# PAGE1old.net
KiCad netlist of a schematic drawn in Altium Designer
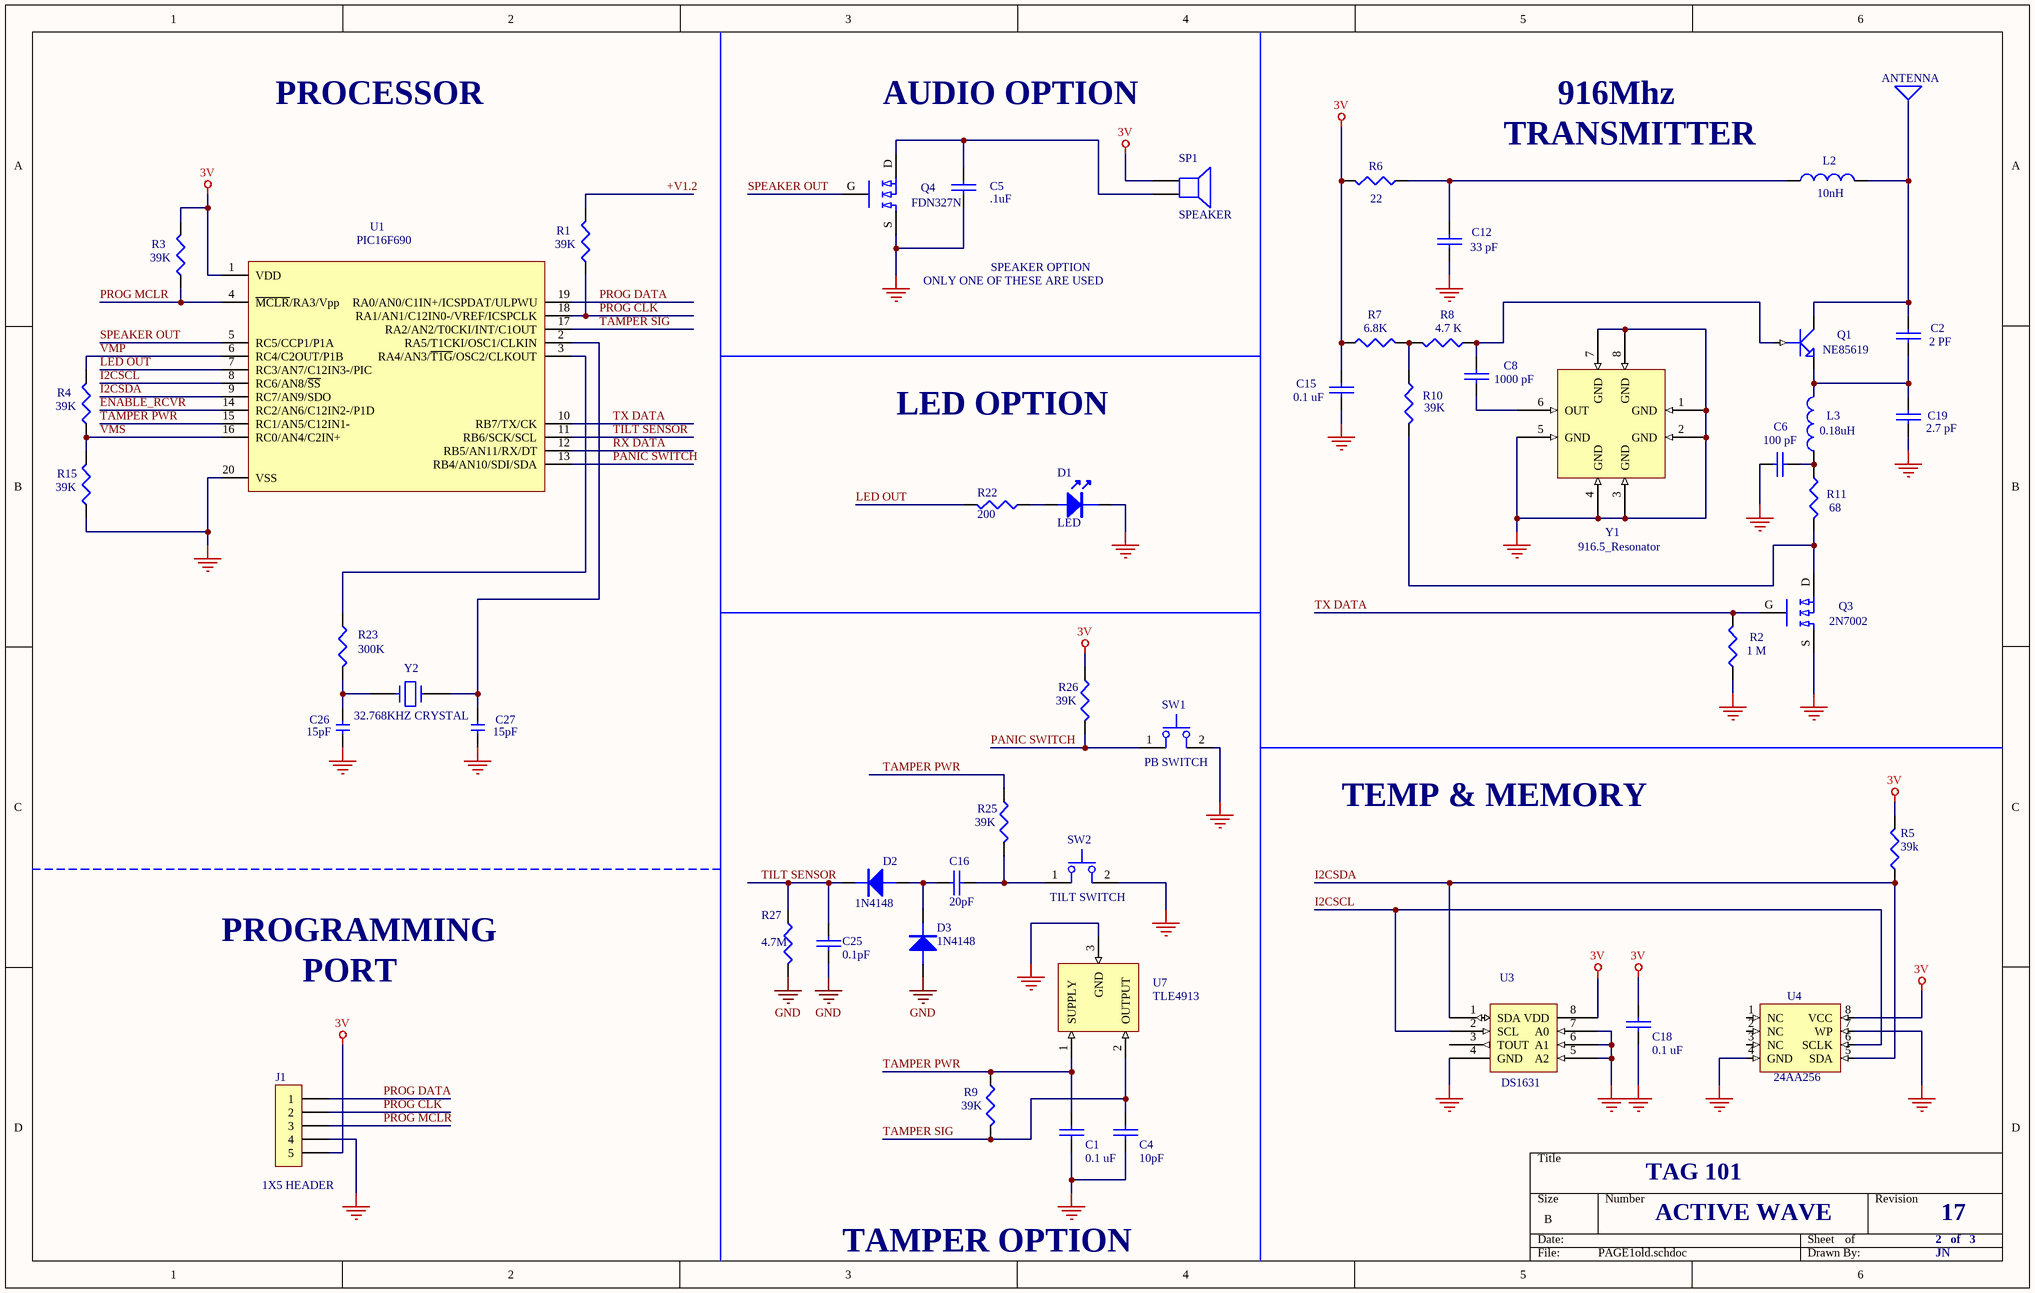
[diagram p0: PAGE1old.schdoc]

(export (version "E")
  (design (tool "Eeschema 10.0.6"))
  (components
    (comp (ref "C1")
      (value "0.1 uF")
      (footprint "0603")
      (description "Capacitor")
      (libsource (lib "*") (part "CAP"))
    )
    (comp (ref "C2")
      (value "2 PF")
      (footprint "0603")
      (description "Capacitor")
      (libsource (lib "*") (part "CAP"))
    )
    (comp (ref "C4")
      (value "10pF")
      (footprint "0603")
      (description "Capacitor")
      (libsource (lib "*") (part "CAP"))
    )
    (comp (ref "C5")
      (value ".1uF")
      (footprint "0603")
      (description "Capacitor")
      (libsource (lib "*") (part "CAP"))
    )
    (comp (ref "C6")
      (value "100 pF")
      (footprint "0603")
      (description "Capacitor")
      (libsource (lib "*") (part "CAP"))
    )
    (comp (ref "C8")
      (value "1000 pF")
      (footprint "0603")
      (description "Capacitor")
      (libsource (lib "*") (part "CAP"))
    )
    (comp (ref "C12")
      (value "33 pF")
      (footprint "0603")
      (description "Capacitor")
      (libsource (lib "*") (part "CAP"))
    )
    (comp (ref "C15")
      (value "0.1 uF")
      (footprint "0603")
      (description "Capacitor")
      (libsource (lib "*") (part "CAP"))
    )
    (comp (ref "C16")
      (value "20pF")
      (footprint "0603")
      (description "Capacitor")
      (libsource (lib "*") (part "CAP"))
    )
    (comp (ref "C18")
      (value "0.1 uF")
      (footprint "0603")
      (description "Capacitor")
      (libsource (lib "*") (part "CAP"))
    )
    (comp (ref "C19")
      (value "2.7 pF")
      (footprint "0603")
      (description "Capacitor")
      (libsource (lib "*") (part "CAP"))
    )
    (comp (ref "C25")
      (value "0.1pF")
      (footprint "0603")
      (description "Capacitor")
      (libsource (lib "*") (part "CAP"))
    )
    (comp (ref "C26") (value "15pF") (footprint "0603") (libsource (lib "*") (part "C")))
    (comp (ref "C27") (value "15pF") (footprint "0603") (libsource (lib "*") (part "C")))
    (comp (ref "D1") (value "LED") (footprint "LED STANLEY H_1105W") (libsource (lib "*") (part "LED")))
    (comp (ref "D2")
      (value "1N4148")
      (footprint "sod123_021405")
      (description "Diode")
      (libsource (lib "*") (part "DIODE"))
    )
    (comp (ref "D3")
      (value "1N4148")
      (footprint "sod123_021405")
      (description "Diode")
      (libsource (lib "*") (part "DIODE"))
    )
    (comp (ref "J1")
      (value "1X5 HEADER")
      (footprint "1X5 HEADER")
      (description "Connector")
      (libsource (lib "*") (part "CON5"))
    )
    (comp (ref "L2") (value "10nH") (footprint "0603") (libsource (lib "*") (part "INDUCTOR")))
    (comp (ref "L3") (value "0.18uH") (footprint "0603") (libsource (lib "*") (part "INDUCTOR")))
    (comp (ref "Q1")
      (value "NE85619")
      (footprint "3 PIN ULTRA SUPER MINI MOLD")
      (description "NPN Transistor")
      (libsource (lib "*") (part "NPN1"))
    )
    (comp (ref "Q3") (value "2N7002") (libsource (lib "*") (part "FET 2")))
    (comp (ref "Q4") (value "FDN327N") (libsource (lib "*") (part "FET 2")))
    (comp (ref "R1") (value "39K") (footprint "0603") (libsource (lib "*") (part "RESISTOR")))
    (comp (ref "R2") (value "1 M") (footprint "0603") (libsource (lib "*") (part "RESISTOR")))
    (comp (ref "R3") (value "39K") (footprint "0603") (libsource (lib "*") (part "RESISTOR")))
    (comp (ref "R4") (value "39K") (footprint "0603") (libsource (lib "*") (part "RESISTOR")))
    (comp (ref "R5") (value "39k") (footprint "0603") (libsource (lib "*") (part "RESISTOR")))
    (comp (ref "R6") (value "22") (footprint "0603") (libsource (lib "*") (part "RESISTOR")))
    (comp (ref "R7") (value "6.8K") (footprint "0603") (libsource (lib "*") (part "RESISTOR")))
    (comp (ref "R8") (value "4.7 K") (footprint "0603") (libsource (lib "*") (part "RESISTOR")))
    (comp (ref "R9") (value "39K") (footprint "0603") (libsource (lib "*") (part "RESISTOR")))
    (comp (ref "R10") (value "39K") (footprint "0603") (libsource (lib "*") (part "RESISTOR")))
    (comp (ref "R11") (value "68") (footprint "0603") (libsource (lib "*") (part "RES1")))
    (comp (ref "R15") (value "39K") (footprint "0603") (libsource (lib "*") (part "RESISTOR")))
    (comp (ref "R22") (value "200") (footprint "0603") (libsource (lib "*") (part "RES1")))
    (comp (ref "R23") (value "300K") (footprint "0603") (libsource (lib "*") (part "RESISTOR")))
    (comp (ref "R25") (value "39K") (footprint "0603") (libsource (lib "*") (part "RESISTOR")))
    (comp (ref "R26") (value "39K") (footprint "0603") (libsource (lib "*") (part "RESISTOR")))
    (comp (ref "R27") (value "4.7M") (footprint "0603") (libsource (lib "*") (part "RESISTOR")))
    (comp (ref "SP1") (value "SPEAKER") (footprint "SMT_1028-S-R") (libsource (lib "*") (part "SPEAKER")))
    (comp (ref "SW1")
      (value "PB SWITCH")
      (footprint "SWITCH PB REVERSED_082907")
      (libsource (lib "Common") (part "SWITCH PB"))
    )
    (comp (ref "SW2")
      (value "TILT SWITCH")
      (footprint "SQ-SEN-200")
      (libsource (lib "Common") (part "SWITCH PB"))
    )
    (comp (ref "U1") (value "PIC16F690") (libsource (lib "*") (part "PIC16F690")))
    (comp (ref "U3") (value "DS1631") (footprint "SO8 SMALL") (libsource (lib "*") (part "DS1631")))
    (comp (ref "U4") (value "24AA256") (footprint "SO8") (libsource (lib "*") (part "24AA256")))
    (comp (ref "U7") (value "TLE4913") (footprint "SOT23W") (libsource (lib "*") (part "HALL EFFECT SWITCH")))
    (comp (ref "Y1")
      (value "916.5_Resonator")
      (footprint "RESONATOR")
      (libsource (lib "*") (part "RESONATOR"))
    )
    (comp (ref "Y2")
      (value "32.768KHZ CRYSTAL")
      (footprint "CRYSTAL ABRACON ABS07")
      (description "Crystal")
      (libsource (lib "*") (part "CRYSTAL"))
    )
  )
  (nets
    (net (code "1") (name "/+V1.2") (class "Default")
      (node (ref "R1") (pin "2") (pinfunction "2_2") (pintype "passive"))
    )
    (net (code "2") (name "/ENABLE_RCVR") (class "Default")
      (node (ref "U1") (pin "14") (pinfunction "RC2/AN6/C12IN2-/P1D_14") (pintype "passive"))
    )
    (net (code "3") (name "/I2CSCL") (class "Default")
      (node (ref "U1") (pin "8") (pinfunction "RC6/AN8/~{SS}_8") (pintype "passive"))
      (node (ref "U3") (pin "2") (pinfunction "SCL_2") (pintype "input"))
      (node (ref "U4") (pin "6") (pinfunction "SCLK_6") (pintype "input"))
    )
    (net (code "4") (name "/I2CSDA") (class "Default")
      (node (ref "R5") (pin "1") (pinfunction "1_1") (pintype "passive"))
      (node (ref "U1") (pin "9") (pinfunction "RC7/AN9/SDO_9") (pintype "passive"))
      (node (ref "U3") (pin "1") (pinfunction "SDA_1") (pintype "bidirectional"))
      (node (ref "U4") (pin "5") (pinfunction "SDA_5") (pintype "input"))
    )
    (net (code "5") (name "/LED OUT") (class "Default")
      (node (ref "R22") (pin "2") (pinfunction "2_2") (pintype "passive"))
      (node (ref "U1") (pin "7") (pinfunction "RC3/AN7/C12IN3-/PIC_7") (pintype "passive"))
    )
    (net (code "6") (name "/PANIC SWITCH") (class "Default")
      (node (ref "R26") (pin "2") (pinfunction "2_2") (pintype "passive"))
      (node (ref "SW1") (pin "1") (pinfunction "1_1") (pintype "passive"))
      (node (ref "U1") (pin "13") (pinfunction "RB4/AN10/SDI/SDA_13") (pintype "passive"))
    )
    (net (code "7") (name "/PROG CLK") (class "Default")
      (node (ref "J1") (pin "2") (pinfunction "2_2") (pintype "passive"))
      (node (ref "R1") (pin "1") (pinfunction "1_1") (pintype "passive"))
      (node (ref "U1") (pin "18") (pinfunction "RA1/AN1/C12IN0-/VREF/ICSPCLK_18") (pintype "passive"))
    )
    (net (code "8") (name "/PROG DATA") (class "Default")
      (node (ref "J1") (pin "1") (pinfunction "1_1") (pintype "passive"))
      (node (ref "U1") (pin "19") (pinfunction "RA0/AN0/C1IN+/ICSPDAT/ULPWU_19") (pintype "passive"))
    )
    (net (code "9") (name "/PROG MCLR") (class "Default")
      (node (ref "J1") (pin "3") (pinfunction "3_3") (pintype "passive"))
      (node (ref "R3") (pin "1") (pinfunction "1_1") (pintype "passive"))
      (node (ref "U1") (pin "4") (pinfunction "~{MCLR}/RA3/Vpp_4") (pintype "passive"))
    )
    (net (code "10") (name "/RX DATA") (class "Default")
      (node (ref "U1") (pin "12") (pinfunction "RB5/AN11/RX/DT_12") (pintype "passive"))
    )
    (net (code "11") (name "/SPEAKER OUT") (class "Default")
      (node (ref "Q4") (pin "G") (pinfunction "G_G") (pintype "passive"))
      (node (ref "U1") (pin "5") (pinfunction "RC5/CCP1/P1A_5") (pintype "passive"))
    )
    (net (code "12") (name "/TAMPER PWR") (class "Default")
      (node (ref "C1") (pin "1") (pinfunction "1_1") (pintype "passive"))
      (node (ref "R25") (pin "1") (pinfunction "1_1") (pintype "passive"))
      (node (ref "R9") (pin "1") (pinfunction "1_1") (pintype "passive"))
      (node (ref "U1") (pin "15") (pinfunction "RC1/AN5/C12IN1-_15") (pintype "passive"))
      (node (ref "U7") (pin "1") (pinfunction "SUPPLY_1") (pintype "input"))
    )
    (net (code "13") (name "/TAMPER SIG") (class "Default")
      (node (ref "C4") (pin "1") (pinfunction "1_1") (pintype "passive"))
      (node (ref "R9") (pin "2") (pinfunction "2_2") (pintype "passive"))
      (node (ref "U1") (pin "17") (pinfunction "RA2/AN2/T0CKI/INT/C1OUT_17") (pintype "passive"))
      (node (ref "U7") (pin "2") (pinfunction "OUTPUT_2") (pintype "input"))
    )
    (net (code "14") (name "/TILT SENSOR") (class "Default")
      (node (ref "C25") (pin "1") (pinfunction "1_1") (pintype "passive"))
      (node (ref "D2") (pin "K") (pinfunction "K_K") (pintype "passive"))
      (node (ref "R27") (pin "1") (pinfunction "1_1") (pintype "passive"))
      (node (ref "U1") (pin "11") (pinfunction "RB6/SCK/SCL_11") (pintype "passive"))
    )
    (net (code "15") (name "/TX DATA") (class "Default")
      (node (ref "Q3") (pin "G") (pinfunction "G_G") (pintype "passive"))
      (node (ref "R2") (pin "2") (pinfunction "2_2") (pintype "passive"))
      (node (ref "U1") (pin "10") (pinfunction "RB7/TX/CK_10") (pintype "passive"))
    )
    (net (code "16") (name "/VMP") (class "Default")
      (node (ref "R4") (pin "2") (pinfunction "2_2") (pintype "passive"))
      (node (ref "U1") (pin "6") (pinfunction "RC4/C2OUT/P1B_6") (pintype "passive"))
    )
    (net (code "17") (name "/VMS") (class "Default")
      (node (ref "R15") (pin "2") (pinfunction "2_2") (pintype "passive"))
      (node (ref "R4") (pin "1") (pinfunction "1_1") (pintype "passive"))
      (node (ref "U1") (pin "16") (pinfunction "RC0/AN4/C2IN+_16") (pintype "passive"))
    )
    (net (code "18") (name "3V") (class "Default")
      (node (ref "C15") (pin "1") (pinfunction "1_1") (pintype "passive"))
      (node (ref "C18") (pin "1") (pinfunction "1_1") (pintype "passive"))
      (node (ref "J1") (pin "5") (pinfunction "5_5") (pintype "passive"))
      (node (ref "R26") (pin "1") (pinfunction "1_1") (pintype "passive"))
      (node (ref "R3") (pin "2") (pinfunction "2_2") (pintype "passive"))
      (node (ref "R5") (pin "2") (pinfunction "2_2") (pintype "passive"))
      (node (ref "R6") (pin "2") (pinfunction "2_2") (pintype "passive"))
      (node (ref "R7") (pin "1") (pinfunction "1_1") (pintype "passive"))
      (node (ref "SP1") (pin "1") (pinfunction "1_1") (pintype "passive"))
      (node (ref "U1") (pin "1") (pinfunction "VDD_1") (pintype "passive"))
      (node (ref "U3") (pin "8") (pinfunction "VDD_8") (pintype "power_in"))
      (node (ref "U4") (pin "8") (pinfunction "VCC_8") (pintype "input"))
    )
    (net (code "19") (name "GND") (class "Default")
      (node (ref "C1") (pin "2") (pinfunction "2_2") (pintype "passive"))
      (node (ref "C12") (pin "2") (pinfunction "2_2") (pintype "passive"))
      (node (ref "C15") (pin "2") (pinfunction "2_2") (pintype "passive"))
      (node (ref "C18") (pin "2") (pinfunction "2_2") (pintype "passive"))
      (node (ref "C19") (pin "2") (pinfunction "2_2") (pintype "passive"))
      (node (ref "C25") (pin "2") (pinfunction "2_2") (pintype "passive"))
      (node (ref "C26") (pin "1") (pinfunction "1_1") (pintype "passive"))
      (node (ref "C27") (pin "1") (pinfunction "1_1") (pintype "passive"))
      (node (ref "C4") (pin "2") (pinfunction "2_2") (pintype "passive"))
      (node (ref "C5") (pin "2") (pinfunction "2_2") (pintype "passive"))
      (node (ref "C6") (pin "1") (pinfunction "1_1") (pintype "passive"))
      (node (ref "D1") (pin "K") (pinfunction "K_K") (pintype "passive"))
      (node (ref "D3") (pin "A") (pinfunction "A_A") (pintype "passive"))
      (node (ref "J1") (pin "4") (pinfunction "4_4") (pintype "passive"))
      (node (ref "Q3") (pin "S") (pinfunction "S_S") (pintype "passive"))
      (node (ref "Q4") (pin "S") (pinfunction "S_S") (pintype "passive"))
      (node (ref "R15") (pin "1") (pinfunction "1_1") (pintype "passive"))
      (node (ref "R2") (pin "1") (pinfunction "1_1") (pintype "passive"))
      (node (ref "R27") (pin "2") (pinfunction "2_2") (pintype "passive"))
      (node (ref "SW1") (pin "2") (pinfunction "2_2") (pintype "passive"))
      (node (ref "SW2") (pin "2") (pinfunction "2_2") (pintype "passive"))
      (node (ref "U1") (pin "20") (pinfunction "VSS_20") (pintype "passive"))
      (node (ref "U3") (pin "4") (pinfunction "GND_4") (pintype "power_in"))
      (node (ref "U3") (pin "5") (pinfunction "A2_5") (pintype "input"))
      (node (ref "U3") (pin "6") (pinfunction "A1_6") (pintype "input"))
      (node (ref "U3") (pin "7") (pinfunction "A0_7") (pintype "input"))
      (node (ref "U4") (pin "4") (pinfunction "GND_4") (pintype "input"))
      (node (ref "U4") (pin "7") (pinfunction "WP_7") (pintype "input"))
      (node (ref "U7") (pin "3") (pinfunction "GND_3") (pintype "input"))
      (node (ref "Y1") (pin "1") (pinfunction "GND_1") (pintype "input"))
      (node (ref "Y1") (pin "2") (pinfunction "GND_2") (pintype "input"))
      (node (ref "Y1") (pin "3") (pinfunction "GND_3") (pintype "input"))
      (node (ref "Y1") (pin "4") (pinfunction "GND_4") (pintype "input"))
      (node (ref "Y1") (pin "5") (pinfunction "GND_5") (pintype "input"))
      (node (ref "Y1") (pin "7") (pinfunction "GND_7") (pintype "input"))
      (node (ref "Y1") (pin "8") (pinfunction "GND_8") (pintype "input"))
    )
    (net (code "20") (name "Net-(C2-Pad1)") (class "Default")
      (node (ref "C2") (pin "1") (pinfunction "1_1") (pintype "passive"))
      (node (ref "L2") (pin "2") (pinfunction "2_2") (pintype "passive"))
      (node (ref "Q1") (pin "C") (pinfunction "C_C") (pintype "passive"))
    )
    (net (code "21") (name "Net-(C5-Pad1)") (class "Default")
      (node (ref "C5") (pin "1") (pinfunction "1_1") (pintype "passive"))
      (node (ref "Q4") (pin "D") (pinfunction "D_D") (pintype "passive"))
      (node (ref "SP1") (pin "2") (pinfunction "2_2") (pintype "passive"))
    )
    (net (code "22") (name "Net-(C6-Pad2)") (class "Default")
      (node (ref "C6") (pin "2") (pinfunction "2_2") (pintype "passive"))
      (node (ref "L3") (pin "1") (pinfunction "1_1") (pintype "passive"))
      (node (ref "R11") (pin "1") (pinfunction "1_1") (pintype "passive"))
    )
    (net (code "23") (name "Net-(C8-Pad1)") (class "Default")
      (node (ref "C8") (pin "1") (pinfunction "1_1") (pintype "passive"))
      (node (ref "Q1") (pin "B") (pinfunction "B_B") (pintype "input"))
      (node (ref "R8") (pin "1") (pinfunction "1_1") (pintype "passive"))
    )
    (net (code "24") (name "Net-(C12-Pad1)") (class "Default")
      (node (ref "C12") (pin "1") (pinfunction "1_1") (pintype "passive"))
      (node (ref "L2") (pin "1") (pinfunction "1_1") (pintype "passive"))
      (node (ref "R6") (pin "1") (pinfunction "1_1") (pintype "passive"))
    )
    (net (code "25") (name "Net-(C16-Pad1)") (class "Default")
      (node (ref "C16") (pin "1") (pinfunction "1_1") (pintype "passive"))
      (node (ref "R25") (pin "2") (pinfunction "2_2") (pintype "passive"))
      (node (ref "SW2") (pin "1") (pinfunction "1_1") (pintype "passive"))
    )
    (net (code "26") (name "Net-(C16-Pad2)") (class "Default")
      (node (ref "C16") (pin "2") (pinfunction "2_2") (pintype "passive"))
      (node (ref "D2") (pin "A") (pinfunction "A_A") (pintype "passive"))
      (node (ref "D3") (pin "K") (pinfunction "K_K") (pintype "passive"))
    )
    (net (code "27") (name "Net-(C19-Pad1)") (class "Default")
      (node (ref "C19") (pin "1") (pinfunction "1_1") (pintype "passive"))
      (node (ref "C2") (pin "2") (pinfunction "2_2") (pintype "passive"))
      (node (ref "L3") (pin "2") (pinfunction "2_2") (pintype "passive"))
      (node (ref "Q1") (pin "E") (pinfunction "E_E") (pintype "passive"))
    )
    (net (code "28") (name "Net-(C26-Pad2)") (class "Default")
      (node (ref "C26") (pin "2") (pinfunction "2_2") (pintype "passive"))
      (node (ref "R23") (pin "2") (pinfunction "2_2") (pintype "passive"))
      (node (ref "Y2") (pin "2") (pinfunction "2_2") (pintype "passive"))
    )
    (net (code "29") (name "Net-(D1-PadA)") (class "Default")
      (node (ref "D1") (pin "A") (pinfunction "A_A") (pintype "passive"))
      (node (ref "R22") (pin "1") (pinfunction "1_1") (pintype "passive"))
    )
    (net (code "30") (name "Net-(Q3-PadD)") (class "Default")
      (node (ref "Q3") (pin "D") (pinfunction "D_D") (pintype "passive"))
      (node (ref "R10") (pin "2") (pinfunction "2_2") (pintype "passive"))
      (node (ref "R11") (pin "2") (pinfunction "2_2") (pintype "passive"))
    )
    (net (code "31") (name "Net-(R10-Pad1)") (class "Default")
      (node (ref "R10") (pin "1") (pinfunction "1_1") (pintype "passive"))
      (node (ref "R7") (pin "2") (pinfunction "2_2") (pintype "passive"))
      (node (ref "R8") (pin "2") (pinfunction "2_2") (pintype "passive"))
    )
    (net (code "32") (name "Net-(U1-RA4{slash}AN3{slash}~{T1G}{slash}OSC2{slash}CLKOUT)") (class "Default")
      (node (ref "R23") (pin "1") (pinfunction "1_1") (pintype "passive"))
      (node (ref "U1") (pin "3") (pinfunction "RA4/AN3/~{T1G}/OSC2/CLKOUT_3") (pintype "passive"))
    )
    (net (code "33") (name "Net-(U1-RA5{slash}T1CKI{slash}OSC1{slash}CLKIN)") (class "Default")
      (node (ref "C27") (pin "2") (pinfunction "2_2") (pintype "passive"))
      (node (ref "U1") (pin "2") (pinfunction "RA5/T1CKI/OSC1/CLKIN_2") (pintype "passive"))
      (node (ref "Y2") (pin "1") (pinfunction "1_1") (pintype "passive"))
    )
    (net (code "34") (name "Net-(Y1-OUT)") (class "Default")
      (node (ref "C8") (pin "2") (pinfunction "2_2") (pintype "passive"))
      (node (ref "Y1") (pin "6") (pinfunction "OUT_6") (pintype "input"))
    )
    (net (code "35") (name "unconnected-(U3-TOUT-Pad3)") (class "Default")
      (node (ref "U3") (pin "3") (pinfunction "TOUT_3") (pintype "output"))
    )
    (net (code "36") (name "unconnected-(U4-NC-Pad1)") (class "Default")
      (node (ref "U4") (pin "1") (pinfunction "NC_1") (pintype "input"))
    )
    (net (code "37") (name "unconnected-(U4-NC-Pad2)") (class "Default")
      (node (ref "U4") (pin "2") (pinfunction "NC_2") (pintype "input"))
    )
    (net (code "38") (name "unconnected-(U4-NC-Pad3)") (class "Default")
      (node (ref "U4") (pin "3") (pinfunction "NC_3") (pintype "input"))
    )
  )
)
